# Mux_Demux.net
KiCad netlist of a schematic drawn in Altium Designer
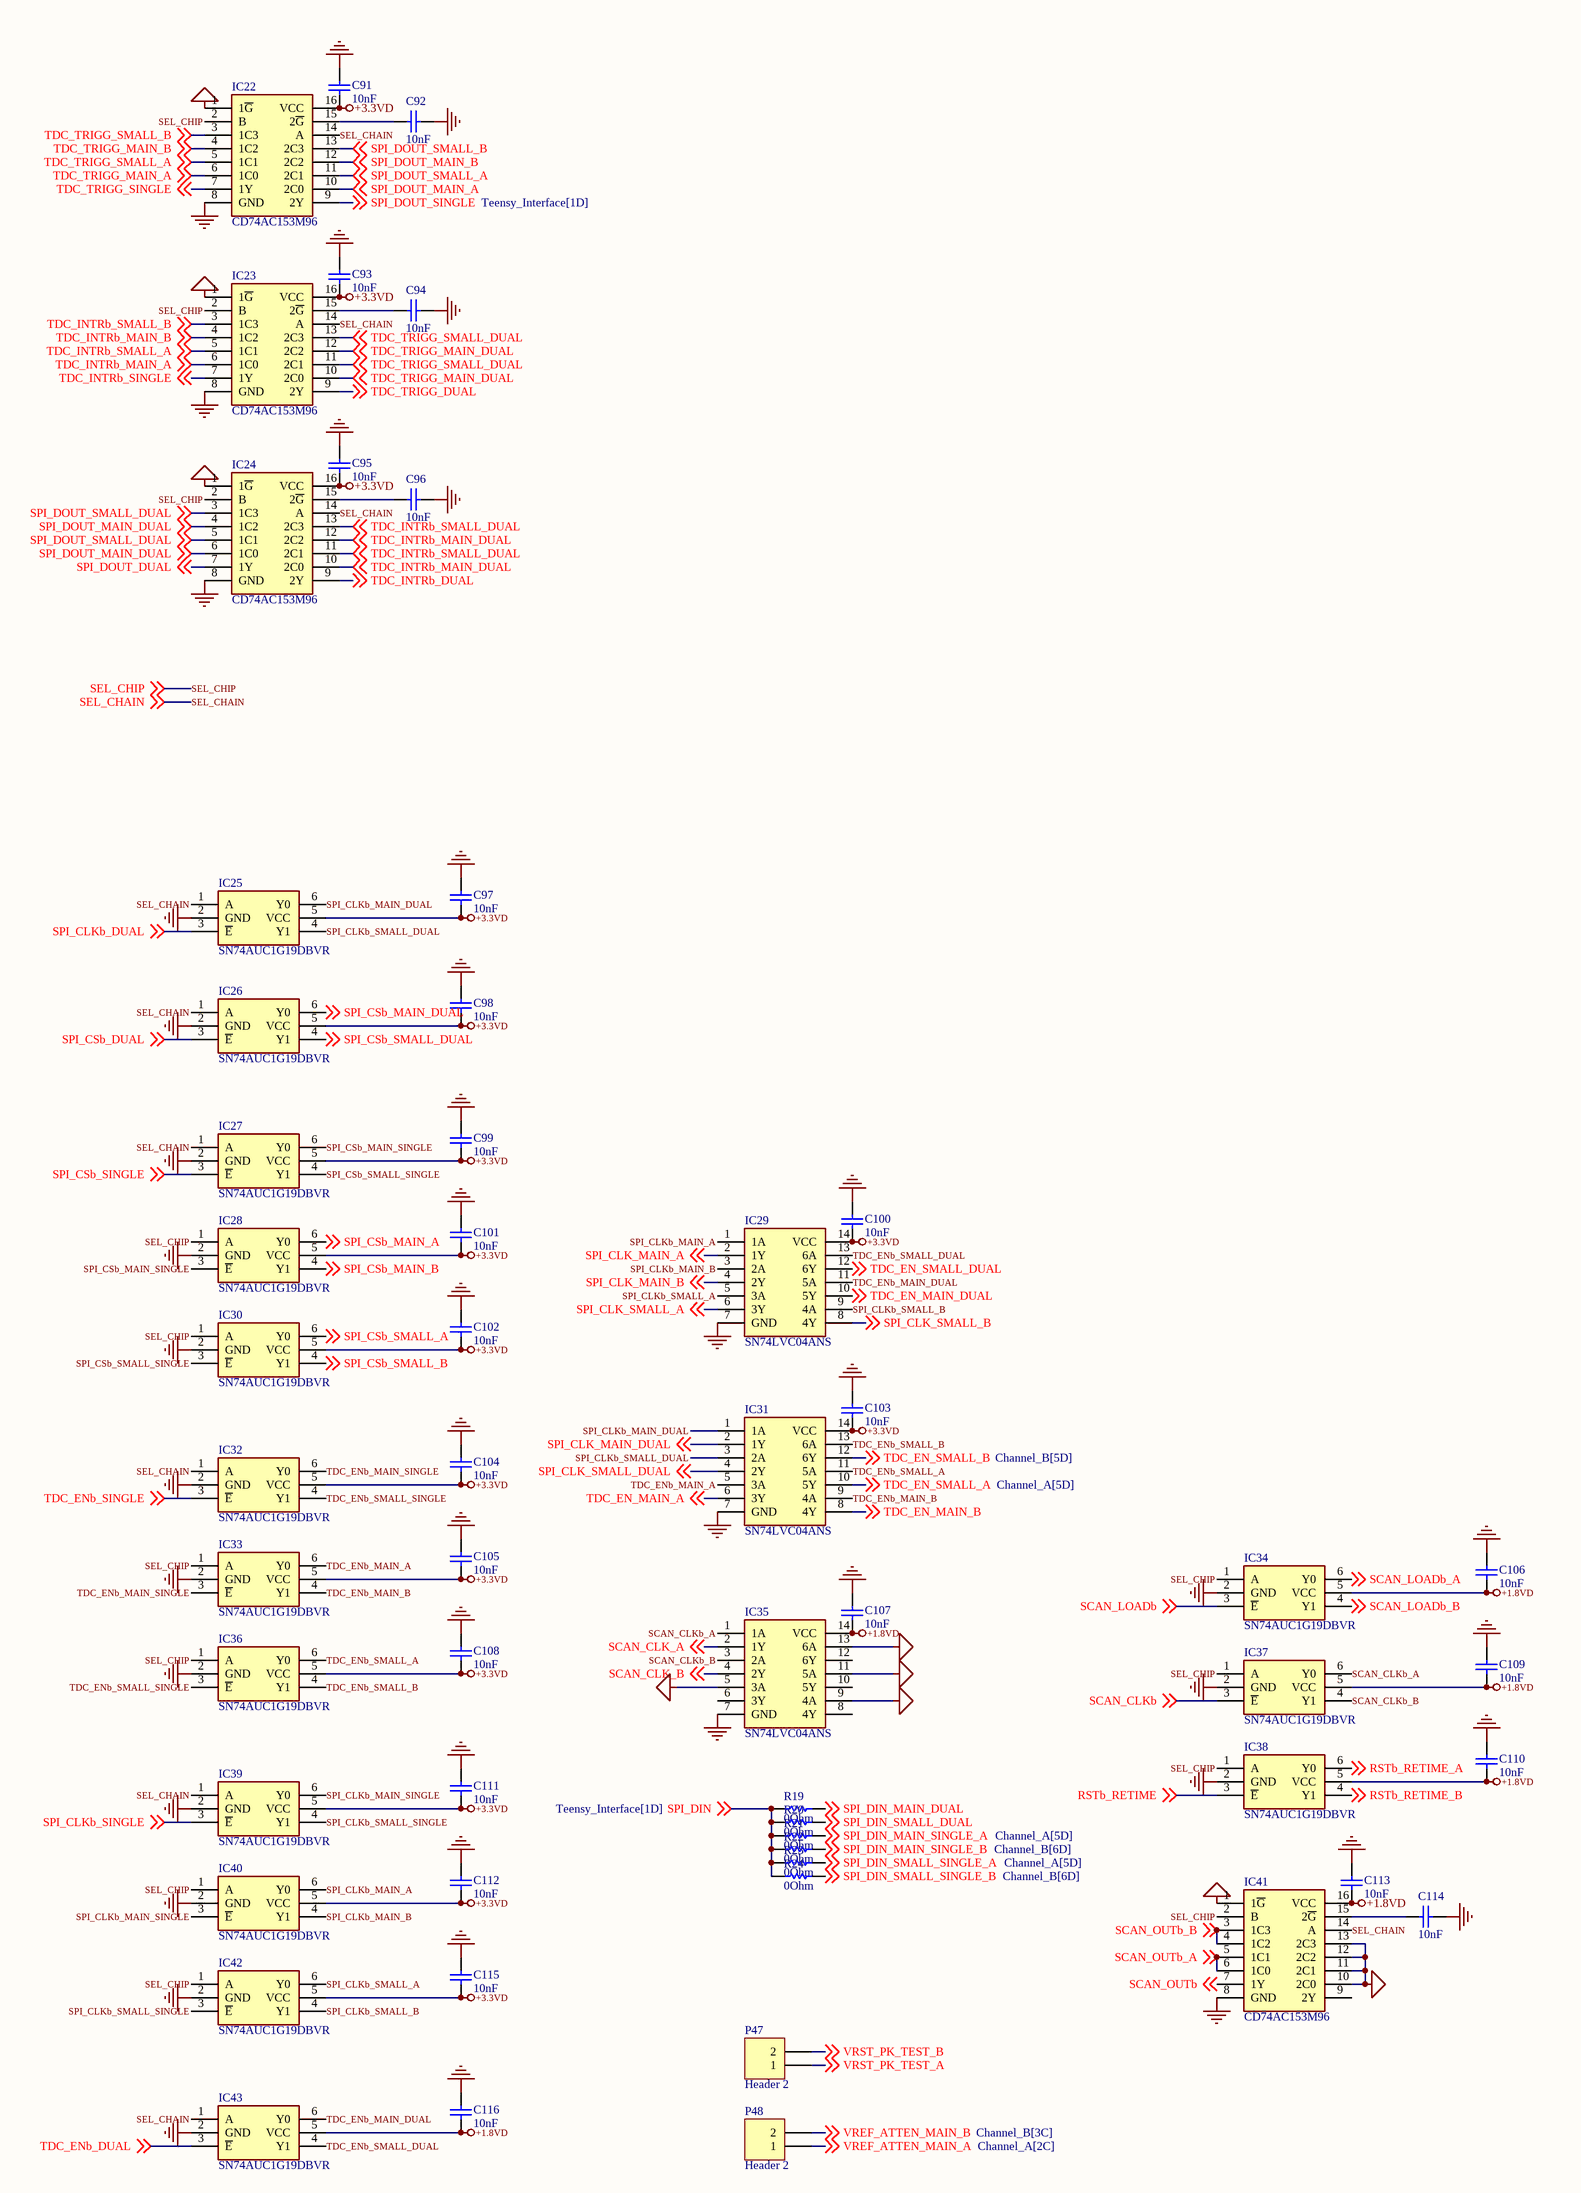
[diagram p0: Mux_Demux.SchDoc]

(export (version "E")
  (design (tool "Eeschema 10.0.6"))
  (components
    (comp (ref "C91")
      (value "10nF")
      (footprint "CAPC1608X90X35ML10T15")
      (description "0603")
      (fields (field (name "MANUFACTURER") "Murata"))
      (libsource (lib "Altium Content Vault") (part "CAP-NP-2"))
    )
    (comp (ref "C92")
      (value "10nF")
      (footprint "CAPC1608X90X35ML10T15")
      (description "0603")
      (fields (field (name "MANUFACTURER") "Murata"))
      (libsource (lib "Altium Content Vault") (part "CAP-NP-2"))
    )
    (comp (ref "C93")
      (value "10nF")
      (footprint "CAPC1608X90X35ML10T15")
      (description "0603")
      (fields (field (name "MANUFACTURER") "Murata"))
      (libsource (lib "Altium Content Vault") (part "CAP-NP-2"))
    )
    (comp (ref "C94")
      (value "10nF")
      (footprint "CAPC1608X90X35ML10T15")
      (description "0603")
      (fields (field (name "MANUFACTURER") "Murata"))
      (libsource (lib "Altium Content Vault") (part "CAP-NP-2"))
    )
    (comp (ref "C95")
      (value "10nF")
      (footprint "CAPC1608X90X35ML10T15")
      (description "0603")
      (fields (field (name "MANUFACTURER") "Murata"))
      (libsource (lib "Altium Content Vault") (part "CAP-NP-2"))
    )
    (comp (ref "C96")
      (value "10nF")
      (footprint "CAPC1608X90X35ML10T15")
      (description "0603")
      (fields (field (name "MANUFACTURER") "Murata"))
      (libsource (lib "Altium Content Vault") (part "CAP-NP-2"))
    )
    (comp (ref "C97")
      (value "10nF")
      (footprint "CAPC1608X90X35ML10T15")
      (description "0603")
      (fields (field (name "MANUFACTURER") "Murata"))
      (libsource (lib "Altium Content Vault") (part "CAP-NP-2"))
    )
    (comp (ref "C98")
      (value "10nF")
      (footprint "CAPC1608X90X35ML10T15")
      (description "0603")
      (fields (field (name "MANUFACTURER") "Murata"))
      (libsource (lib "Altium Content Vault") (part "CAP-NP-2"))
    )
    (comp (ref "C99")
      (value "10nF")
      (footprint "CAPC1608X90X35ML10T15")
      (description "0603")
      (fields (field (name "MANUFACTURER") "Murata"))
      (libsource (lib "Altium Content Vault") (part "CAP-NP-2"))
    )
    (comp (ref "C100")
      (value "10nF")
      (footprint "CAPC1608X90X35ML10T15")
      (description "0603")
      (fields (field (name "MANUFACTURER") "Murata"))
      (libsource (lib "Altium Content Vault") (part "CAP-NP-2"))
    )
    (comp (ref "C101")
      (value "10nF")
      (footprint "CAPC1608X90X35ML10T15")
      (description "0603")
      (fields (field (name "MANUFACTURER") "Murata"))
      (libsource (lib "Altium Content Vault") (part "CAP-NP-2"))
    )
    (comp (ref "C102")
      (value "10nF")
      (footprint "CAPC1608X90X35ML10T15")
      (description "0603")
      (fields (field (name "MANUFACTURER") "Murata"))
      (libsource (lib "Altium Content Vault") (part "CAP-NP-2"))
    )
    (comp (ref "C103")
      (value "10nF")
      (footprint "CAPC1608X90X35ML10T15")
      (description "0603")
      (fields (field (name "MANUFACTURER") "Murata"))
      (libsource (lib "Altium Content Vault") (part "CAP-NP-2"))
    )
    (comp (ref "C104")
      (value "10nF")
      (footprint "CAPC1608X90X35ML10T15")
      (description "0603")
      (fields (field (name "MANUFACTURER") "Murata"))
      (libsource (lib "Altium Content Vault") (part "CAP-NP-2"))
    )
    (comp (ref "C105")
      (value "10nF")
      (footprint "CAPC1608X90X35ML10T15")
      (description "0603")
      (fields (field (name "MANUFACTURER") "Murata"))
      (libsource (lib "Altium Content Vault") (part "CAP-NP-2"))
    )
    (comp (ref "C106")
      (value "10nF")
      (footprint "CAPC1608X90X35ML10T15")
      (description "0603")
      (fields (field (name "MANUFACTURER") "Murata"))
      (libsource (lib "Altium Content Vault") (part "CAP-NP-2"))
    )
    (comp (ref "C107")
      (value "10nF")
      (footprint "CAPC1608X90X35ML10T15")
      (description "0603")
      (fields (field (name "MANUFACTURER") "Murata"))
      (libsource (lib "Altium Content Vault") (part "CAP-NP-2"))
    )
    (comp (ref "C108")
      (value "10nF")
      (footprint "CAPC1608X90X35ML10T15")
      (description "0603")
      (fields (field (name "MANUFACTURER") "Murata"))
      (libsource (lib "Altium Content Vault") (part "CAP-NP-2"))
    )
    (comp (ref "C109")
      (value "10nF")
      (footprint "CAPC1608X90X35ML10T15")
      (description "0603")
      (fields (field (name "MANUFACTURER") "Murata"))
      (libsource (lib "Altium Content Vault") (part "CAP-NP-2"))
    )
    (comp (ref "C110")
      (value "10nF")
      (footprint "CAPC1608X90X35ML10T15")
      (description "0603")
      (fields (field (name "MANUFACTURER") "Murata"))
      (libsource (lib "Altium Content Vault") (part "CAP-NP-2"))
    )
    (comp (ref "C111")
      (value "10nF")
      (footprint "CAPC1608X90X35ML10T15")
      (description "0603")
      (fields (field (name "MANUFACTURER") "Murata"))
      (libsource (lib "Altium Content Vault") (part "CAP-NP-2"))
    )
    (comp (ref "C112")
      (value "10nF")
      (footprint "CAPC1608X90X35ML10T15")
      (description "0603")
      (fields (field (name "MANUFACTURER") "Murata"))
      (libsource (lib "Altium Content Vault") (part "CAP-NP-2"))
    )
    (comp (ref "C113")
      (value "10nF")
      (footprint "CAPC1608X90X35ML10T15")
      (description "0603")
      (fields (field (name "MANUFACTURER") "Murata"))
      (libsource (lib "Altium Content Vault") (part "CAP-NP-2"))
    )
    (comp (ref "C114")
      (value "10nF")
      (footprint "CAPC1608X90X35ML10T15")
      (description "0603")
      (fields (field (name "MANUFACTURER") "Murata"))
      (libsource (lib "Altium Content Vault") (part "CAP-NP-2"))
    )
    (comp (ref "C115")
      (value "10nF")
      (footprint "CAPC1608X90X35ML10T15")
      (description "0603")
      (fields (field (name "MANUFACTURER") "Murata"))
      (libsource (lib "Altium Content Vault") (part "CAP-NP-2"))
    )
    (comp (ref "C116")
      (value "10nF")
      (footprint "CAPC1608X90X35ML10T15")
      (description "0603")
      (fields (field (name "MANUFACTURER") "Murata"))
      (libsource (lib "Altium Content Vault") (part "CAP-NP-2"))
    )
    (comp (ref "IC22")
      (value "CD74AC153M96")
      (footprint "SamacSys:SOIC127P600X175-16N")
      (description "Encoders, Decoders, Multiplexers & Demultiplexers Dual 4-Input")
      (fields (field (name "MOUSER PART NUMBER") "595-CD74AC153M96"))
      (libsource (lib "*") (part "CD74AC153M96"))
    )
    (comp (ref "IC23")
      (value "CD74AC153M96")
      (footprint "SamacSys:SOIC127P600X175-16N")
      (description "Encoders, Decoders, Multiplexers & Demultiplexers Dual 4-Input")
      (fields (field (name "MOUSER PART NUMBER") "595-CD74AC153M96"))
      (libsource (lib "*") (part "CD74AC153M96"))
    )
    (comp (ref "IC24")
      (value "CD74AC153M96")
      (footprint "SamacSys:SOIC127P600X175-16N")
      (description "Encoders, Decoders, Multiplexers & Demultiplexers Dual 4-Input")
      (fields (field (name "MOUSER PART NUMBER") "595-CD74AC153M96"))
      (libsource (lib "*") (part "CD74AC153M96"))
    )
    (comp (ref "IC25")
      (value "SN74AUC1G19DBVR")
      (footprint "SamacSys:SOT95P280X145-6N")
      (description "Encoders, Decoders, Multiplexers & Demultiplexers 1 of 2 Decoder DeMultxe")
      (fields (field (name "MOUSER PART NUMBER") "595-SN74AUC1G19DBVR"))
      (libsource (lib "*") (part "SN74AUC1G19DBVR"))
    )
    (comp (ref "IC26")
      (value "SN74AUC1G19DBVR")
      (footprint "SamacSys:SOT95P280X145-6N")
      (description "Encoders, Decoders, Multiplexers & Demultiplexers 1 of 2 Decoder DeMultxe")
      (fields (field (name "MOUSER PART NUMBER") "595-SN74AUC1G19DBVR"))
      (libsource (lib "*") (part "SN74AUC1G19DBVR"))
    )
    (comp (ref "IC27")
      (value "SN74AUC1G19DBVR")
      (footprint "SamacSys:SOT95P280X145-6N")
      (description "Encoders, Decoders, Multiplexers & Demultiplexers 1 of 2 Decoder DeMultxe")
      (fields (field (name "MOUSER PART NUMBER") "595-SN74AUC1G19DBVR"))
      (libsource (lib "*") (part "SN74AUC1G19DBVR"))
    )
    (comp (ref "IC28")
      (value "SN74AUC1G19DBVR")
      (footprint "SamacSys:SOT95P280X145-6N")
      (description "Encoders, Decoders, Multiplexers & Demultiplexers 1 of 2 Decoder DeMultxe")
      (fields (field (name "MOUSER PART NUMBER") "595-SN74AUC1G19DBVR"))
      (libsource (lib "*") (part "SN74AUC1G19DBVR"))
    )
    (comp (ref "IC29")
      (value "SN74LVC04ANS")
      (footprint "SamacSys:SOIC127P780X200-14N")
      (description "Inverters Hex Inverter")
      (fields (field (name "MOUSER PART NUMBER") "595-SN74LVC04ANS"))
      (libsource (lib "*") (part "SN74LVC04ANS"))
    )
    (comp (ref "IC30")
      (value "SN74AUC1G19DBVR")
      (footprint "SamacSys:SOT95P280X145-6N")
      (description "Encoders, Decoders, Multiplexers & Demultiplexers 1 of 2 Decoder DeMultxe")
      (fields (field (name "MOUSER PART NUMBER") "595-SN74AUC1G19DBVR"))
      (libsource (lib "*") (part "SN74AUC1G19DBVR"))
    )
    (comp (ref "IC31")
      (value "SN74LVC04ANS")
      (footprint "SamacSys:SOIC127P780X200-14N")
      (description "Inverters Hex Inverter")
      (fields (field (name "MOUSER PART NUMBER") "595-SN74LVC04ANS"))
      (libsource (lib "*") (part "SN74LVC04ANS"))
    )
    (comp (ref "IC32")
      (value "SN74AUC1G19DBVR")
      (footprint "SamacSys:SOT95P280X145-6N")
      (description "Encoders, Decoders, Multiplexers & Demultiplexers 1 of 2 Decoder DeMultxe")
      (fields (field (name "MOUSER PART NUMBER") "595-SN74AUC1G19DBVR"))
      (libsource (lib "*") (part "SN74AUC1G19DBVR"))
    )
    (comp (ref "IC33")
      (value "SN74AUC1G19DBVR")
      (footprint "SamacSys:SOT95P280X145-6N")
      (description "Encoders, Decoders, Multiplexers & Demultiplexers 1 of 2 Decoder DeMultxe")
      (fields (field (name "MOUSER PART NUMBER") "595-SN74AUC1G19DBVR"))
      (libsource (lib "*") (part "SN74AUC1G19DBVR"))
    )
    (comp (ref "IC34")
      (value "SN74AUC1G19DBVR")
      (footprint "SamacSys:SOT95P280X145-6N")
      (description "Encoders, Decoders, Multiplexers & Demultiplexers 1 of 2 Decoder DeMultxe")
      (fields (field (name "MOUSER PART NUMBER") "595-SN74AUC1G19DBVR"))
      (libsource (lib "*") (part "SN74AUC1G19DBVR"))
    )
    (comp (ref "IC35")
      (value "SN74LVC04ANS")
      (footprint "SamacSys:SOIC127P780X200-14N")
      (description "Inverters Hex Inverter")
      (fields (field (name "MOUSER PART NUMBER") "595-SN74LVC04ANS"))
      (libsource (lib "*") (part "SN74LVC04ANS"))
    )
    (comp (ref "IC36")
      (value "SN74AUC1G19DBVR")
      (footprint "SamacSys:SOT95P280X145-6N")
      (description "Encoders, Decoders, Multiplexers & Demultiplexers 1 of 2 Decoder DeMultxe")
      (fields (field (name "MOUSER PART NUMBER") "595-SN74AUC1G19DBVR"))
      (libsource (lib "*") (part "SN74AUC1G19DBVR"))
    )
    (comp (ref "IC37")
      (value "SN74AUC1G19DBVR")
      (footprint "SamacSys:SOT95P280X145-6N")
      (description "Encoders, Decoders, Multiplexers & Demultiplexers 1 of 2 Decoder DeMultxe")
      (fields (field (name "MOUSER PART NUMBER") "595-SN74AUC1G19DBVR"))
      (libsource (lib "*") (part "SN74AUC1G19DBVR"))
    )
    (comp (ref "IC38")
      (value "SN74AUC1G19DBVR")
      (footprint "SamacSys:SOT95P280X145-6N")
      (description "Encoders, Decoders, Multiplexers & Demultiplexers 1 of 2 Decoder DeMultxe")
      (fields (field (name "MOUSER PART NUMBER") "595-SN74AUC1G19DBVR"))
      (libsource (lib "*") (part "SN74AUC1G19DBVR"))
    )
    (comp (ref "IC39")
      (value "SN74AUC1G19DBVR")
      (footprint "SamacSys:SOT95P280X145-6N")
      (description "Encoders, Decoders, Multiplexers & Demultiplexers 1 of 2 Decoder DeMultxe")
      (fields (field (name "MOUSER PART NUMBER") "595-SN74AUC1G19DBVR"))
      (libsource (lib "*") (part "SN74AUC1G19DBVR"))
    )
    (comp (ref "IC40")
      (value "SN74AUC1G19DBVR")
      (footprint "SamacSys:SOT95P280X145-6N")
      (description "Encoders, Decoders, Multiplexers & Demultiplexers 1 of 2 Decoder DeMultxe")
      (fields (field (name "MOUSER PART NUMBER") "595-SN74AUC1G19DBVR"))
      (libsource (lib "*") (part "SN74AUC1G19DBVR"))
    )
    (comp (ref "IC41")
      (value "CD74AC153M96")
      (footprint "SamacSys:SOIC127P600X175-16N")
      (description "Encoders, Decoders, Multiplexers & Demultiplexers Dual 4-Input")
      (fields (field (name "MOUSER PART NUMBER") "595-CD74AC153M96"))
      (libsource (lib "*") (part "CD74AC153M96"))
    )
    (comp (ref "IC42")
      (value "SN74AUC1G19DBVR")
      (footprint "SamacSys:SOT95P280X145-6N")
      (description "Encoders, Decoders, Multiplexers & Demultiplexers 1 of 2 Decoder DeMultxe")
      (fields (field (name "MOUSER PART NUMBER") "595-SN74AUC1G19DBVR"))
      (libsource (lib "*") (part "SN74AUC1G19DBVR"))
    )
    (comp (ref "IC43")
      (value "SN74AUC1G19DBVR")
      (footprint "SamacSys:SOT95P280X145-6N")
      (description "Encoders, Decoders, Multiplexers & Demultiplexers 1 of 2 Decoder DeMultxe")
      (fields (field (name "MOUSER PART NUMBER") "595-SN74AUC1G19DBVR"))
      (libsource (lib "*") (part "SN74AUC1G19DBVR"))
    )
    (comp (ref "P47")
      (value "Header 2")
      (footprint "HDR1X2")
      (description "Header, 2-Pin")
      (fields (field (name "PUBLISHER") "Altium Limited"))
      (libsource (lib "Miscellaneous Connectors") (part "Header 2"))
    )
    (comp (ref "P48")
      (value "Header 2")
      (footprint "HDR1X2")
      (description "Header, 2-Pin")
      (fields (field (name "PUBLISHER") "Altium Limited"))
      (libsource (lib "Miscellaneous Connectors") (part "Header 2"))
    )
    (comp (ref "R19")
      (value "0Ohm")
      (footprint "RESC1609X50X30NL8T20")
      (description "0603")
      (fields (field (name "MANUFACTURER") "Vishay Semiconductor"))
      (libsource (lib "Altium Content Vault") (part "RES-2"))
    )
    (comp (ref "R20")
      (value "0Ohm")
      (footprint "RESC1609X50X30NL8T20")
      (description "0603")
      (fields (field (name "MANUFACTURER") "Vishay Semiconductor"))
      (libsource (lib "Altium Content Vault") (part "RES-2"))
    )
    (comp (ref "R21")
      (value "0Ohm")
      (footprint "RESC1609X50X30NL8T20")
      (description "0603")
      (fields (field (name "MANUFACTURER") "Vishay Semiconductor"))
      (libsource (lib "Altium Content Vault") (part "RES-2"))
    )
    (comp (ref "R22")
      (value "0Ohm")
      (footprint "RESC1609X50X30NL8T20")
      (description "0603")
      (fields (field (name "MANUFACTURER") "Vishay Semiconductor"))
      (libsource (lib "Altium Content Vault") (part "RES-2"))
    )
    (comp (ref "R23")
      (value "0Ohm")
      (footprint "RESC1609X50X30NL8T20")
      (description "0603")
      (fields (field (name "MANUFACTURER") "Vishay Semiconductor"))
      (libsource (lib "Altium Content Vault") (part "RES-2"))
    )
    (comp (ref "R24")
      (value "0Ohm")
      (footprint "RESC1609X50X30NL8T20")
      (description "0603")
      (fields (field (name "MANUFACTURER") "Vishay Semiconductor"))
      (libsource (lib "Altium Content Vault") (part "RES-2"))
    )
  )
  (nets
    (net (code "1") (name "+1.8VD") (class "Default")
      (node (ref "C106") (pin "1") (pinfunction "1_1") (pintype "passive"))
      (node (ref "C107") (pin "1") (pinfunction "1_1") (pintype "passive"))
      (node (ref "C109") (pin "1") (pinfunction "1_1") (pintype "passive"))
      (node (ref "C110") (pin "1") (pinfunction "1_1") (pintype "passive"))
      (node (ref "C113") (pin "1") (pinfunction "1_1") (pintype "passive"))
      (node (ref "C116") (pin "1") (pinfunction "1_1") (pintype "passive"))
      (node (ref "IC34") (pin "5") (pinfunction "VCC_5") (pintype "passive"))
      (node (ref "IC35") (pin "14") (pinfunction "VCC_14") (pintype "passive"))
      (node (ref "IC37") (pin "5") (pinfunction "VCC_5") (pintype "passive"))
      (node (ref "IC38") (pin "5") (pinfunction "VCC_5") (pintype "passive"))
      (node (ref "IC41") (pin "16") (pinfunction "VCC_16") (pintype "passive"))
      (node (ref "IC43") (pin "5") (pinfunction "VCC_5") (pintype "passive"))
    )
    (net (code "2") (name "+3.3VD") (class "Default")
      (node (ref "C100") (pin "1") (pinfunction "1_1") (pintype "passive"))
      (node (ref "C101") (pin "1") (pinfunction "1_1") (pintype "passive"))
      (node (ref "C102") (pin "1") (pinfunction "1_1") (pintype "passive"))
      (node (ref "C103") (pin "1") (pinfunction "1_1") (pintype "passive"))
      (node (ref "C104") (pin "1") (pinfunction "1_1") (pintype "passive"))
      (node (ref "C105") (pin "1") (pinfunction "1_1") (pintype "passive"))
      (node (ref "C108") (pin "1") (pinfunction "1_1") (pintype "passive"))
      (node (ref "C111") (pin "1") (pinfunction "1_1") (pintype "passive"))
      (node (ref "C112") (pin "1") (pinfunction "1_1") (pintype "passive"))
      (node (ref "C115") (pin "1") (pinfunction "1_1") (pintype "passive"))
      (node (ref "C91") (pin "1") (pinfunction "1_1") (pintype "passive"))
      (node (ref "C93") (pin "1") (pinfunction "1_1") (pintype "passive"))
      (node (ref "C95") (pin "1") (pinfunction "1_1") (pintype "passive"))
      (node (ref "C97") (pin "1") (pinfunction "1_1") (pintype "passive"))
      (node (ref "C98") (pin "1") (pinfunction "1_1") (pintype "passive"))
      (node (ref "C99") (pin "1") (pinfunction "1_1") (pintype "passive"))
      (node (ref "IC22") (pin "16") (pinfunction "VCC_16") (pintype "passive"))
      (node (ref "IC23") (pin "16") (pinfunction "VCC_16") (pintype "passive"))
      (node (ref "IC24") (pin "16") (pinfunction "VCC_16") (pintype "passive"))
      (node (ref "IC25") (pin "5") (pinfunction "VCC_5") (pintype "passive"))
      (node (ref "IC26") (pin "5") (pinfunction "VCC_5") (pintype "passive"))
      (node (ref "IC27") (pin "5") (pinfunction "VCC_5") (pintype "passive"))
      (node (ref "IC28") (pin "5") (pinfunction "VCC_5") (pintype "passive"))
      (node (ref "IC29") (pin "14") (pinfunction "VCC_14") (pintype "passive"))
      (node (ref "IC30") (pin "5") (pinfunction "VCC_5") (pintype "passive"))
      (node (ref "IC31") (pin "14") (pinfunction "VCC_14") (pintype "passive"))
      (node (ref "IC32") (pin "5") (pinfunction "VCC_5") (pintype "passive"))
      (node (ref "IC33") (pin "5") (pinfunction "VCC_5") (pintype "passive"))
      (node (ref "IC36") (pin "5") (pinfunction "VCC_5") (pintype "passive"))
      (node (ref "IC39") (pin "5") (pinfunction "VCC_5") (pintype "passive"))
      (node (ref "IC40") (pin "5") (pinfunction "VCC_5") (pintype "passive"))
      (node (ref "IC42") (pin "5") (pinfunction "VCC_5") (pintype "passive"))
    )
    (net (code "3") (name "/SCAN_CLKb_A") (class "Default")
      (node (ref "IC35") (pin "1") (pinfunction "1A_1") (pintype "passive"))
      (node (ref "IC37") (pin "6") (pinfunction "Y0_6") (pintype "passive"))
    )
    (net (code "4") (name "/SCAN_CLKb_B") (class "Default")
      (node (ref "IC35") (pin "3") (pinfunction "2A_3") (pintype "passive"))
      (node (ref "IC37") (pin "4") (pinfunction "Y1_4") (pintype "passive"))
    )
    (net (code "5") (name "/SPI_CLKb_MAIN_A") (class "Default")
      (node (ref "IC29") (pin "1") (pinfunction "1A_1") (pintype "passive"))
      (node (ref "IC40") (pin "6") (pinfunction "Y0_6") (pintype "passive"))
    )
    (net (code "6") (name "/SPI_CLKb_MAIN_B") (class "Default")
      (node (ref "IC29") (pin "3") (pinfunction "2A_3") (pintype "passive"))
      (node (ref "IC40") (pin "4") (pinfunction "Y1_4") (pintype "passive"))
    )
    (net (code "7") (name "/SPI_CLKb_MAIN_DUAL") (class "Default")
      (node (ref "IC25") (pin "6") (pinfunction "Y0_6") (pintype "passive"))
      (node (ref "IC31") (pin "1") (pinfunction "1A_1") (pintype "passive"))
    )
    (net (code "8") (name "/SPI_CLKb_MAIN_SINGLE") (class "Default")
      (node (ref "IC39") (pin "6") (pinfunction "Y0_6") (pintype "passive"))
      (node (ref "IC40") (pin "3") (pinfunction "~{E}_3") (pintype "passive"))
    )
    (net (code "9") (name "/SPI_CLKb_SMALL_A") (class "Default")
      (node (ref "IC29") (pin "5") (pinfunction "3A_5") (pintype "passive"))
      (node (ref "IC42") (pin "6") (pinfunction "Y0_6") (pintype "passive"))
    )
    (net (code "10") (name "/SPI_CLKb_SMALL_B") (class "Default")
      (node (ref "IC29") (pin "9") (pinfunction "4A_9") (pintype "passive"))
      (node (ref "IC42") (pin "4") (pinfunction "Y1_4") (pintype "passive"))
    )
    (net (code "11") (name "/SPI_CLKb_SMALL_DUAL") (class "Default")
      (node (ref "IC25") (pin "4") (pinfunction "Y1_4") (pintype "passive"))
      (node (ref "IC31") (pin "3") (pinfunction "2A_3") (pintype "passive"))
    )
    (net (code "12") (name "/SPI_CLKb_SMALL_SINGLE") (class "Default")
      (node (ref "IC39") (pin "4") (pinfunction "Y1_4") (pintype "passive"))
      (node (ref "IC42") (pin "3") (pinfunction "~{E}_3") (pintype "passive"))
    )
    (net (code "13") (name "/SPI_CSb_MAIN_SINGLE") (class "Default")
      (node (ref "IC27") (pin "6") (pinfunction "Y0_6") (pintype "passive"))
      (node (ref "IC28") (pin "3") (pinfunction "~{E}_3") (pintype "passive"))
    )
    (net (code "14") (name "/SPI_CSb_SMALL_SINGLE") (class "Default")
      (node (ref "IC27") (pin "4") (pinfunction "Y1_4") (pintype "passive"))
      (node (ref "IC30") (pin "3") (pinfunction "~{E}_3") (pintype "passive"))
    )
    (net (code "15") (name "/TDC_ENb_MAIN_A") (class "Default")
      (node (ref "IC31") (pin "5") (pinfunction "3A_5") (pintype "passive"))
      (node (ref "IC33") (pin "6") (pinfunction "Y0_6") (pintype "passive"))
    )
    (net (code "16") (name "/TDC_ENb_MAIN_B") (class "Default")
      (node (ref "IC31") (pin "9") (pinfunction "4A_9") (pintype "passive"))
      (node (ref "IC33") (pin "4") (pinfunction "Y1_4") (pintype "passive"))
    )
    (net (code "17") (name "/TDC_ENb_MAIN_DUAL") (class "Default")
      (node (ref "IC29") (pin "11") (pinfunction "5A_11") (pintype "passive"))
      (node (ref "IC43") (pin "6") (pinfunction "Y0_6") (pintype "passive"))
    )
    (net (code "18") (name "/TDC_ENb_MAIN_SINGLE") (class "Default")
      (node (ref "IC32") (pin "6") (pinfunction "Y0_6") (pintype "passive"))
      (node (ref "IC33") (pin "3") (pinfunction "~{E}_3") (pintype "passive"))
    )
    (net (code "19") (name "/TDC_ENb_SMALL_A") (class "Default")
      (node (ref "IC31") (pin "11") (pinfunction "5A_11") (pintype "passive"))
      (node (ref "IC36") (pin "6") (pinfunction "Y0_6") (pintype "passive"))
    )
    (net (code "20") (name "/TDC_ENb_SMALL_B") (class "Default")
      (node (ref "IC31") (pin "13") (pinfunction "6A_13") (pintype "passive"))
      (node (ref "IC36") (pin "4") (pinfunction "Y1_4") (pintype "passive"))
    )
    (net (code "21") (name "/TDC_ENb_SMALL_DUAL") (class "Default")
      (node (ref "IC29") (pin "13") (pinfunction "6A_13") (pintype "passive"))
      (node (ref "IC43") (pin "4") (pinfunction "Y1_4") (pintype "passive"))
    )
    (net (code "22") (name "/TDC_ENb_SMALL_SINGLE") (class "Default")
      (node (ref "IC32") (pin "4") (pinfunction "Y1_4") (pintype "passive"))
      (node (ref "IC36") (pin "3") (pinfunction "~{E}_3") (pintype "passive"))
    )
    (net (code "23") (name "GND") (class "Default")
      (node (ref "C100") (pin "2") (pinfunction "2_2") (pintype "passive"))
      (node (ref "C101") (pin "2") (pinfunction "2_2") (pintype "passive"))
      (node (ref "C102") (pin "2") (pinfunction "2_2") (pintype "passive"))
      (node (ref "C103") (pin "2") (pinfunction "2_2") (pintype "passive"))
      (node (ref "C104") (pin "2") (pinfunction "2_2") (pintype "passive"))
      (node (ref "C105") (pin "2") (pinfunction "2_2") (pintype "passive"))
      (node (ref "C106") (pin "2") (pinfunction "2_2") (pintype "passive"))
      (node (ref "C107") (pin "2") (pinfunction "2_2") (pintype "passive"))
      (node (ref "C108") (pin "2") (pinfunction "2_2") (pintype "passive"))
      (node (ref "C109") (pin "2") (pinfunction "2_2") (pintype "passive"))
      (node (ref "C110") (pin "2") (pinfunction "2_2") (pintype "passive"))
      (node (ref "C111") (pin "2") (pinfunction "2_2") (pintype "passive"))
      (node (ref "C112") (pin "2") (pinfunction "2_2") (pintype "passive"))
      (node (ref "C113") (pin "2") (pinfunction "2_2") (pintype "passive"))
      (node (ref "C114") (pin "2") (pinfunction "2_2") (pintype "passive"))
      (node (ref "C115") (pin "2") (pinfunction "2_2") (pintype "passive"))
      (node (ref "C116") (pin "2") (pinfunction "2_2") (pintype "passive"))
      (node (ref "C91") (pin "2") (pinfunction "2_2") (pintype "passive"))
      (node (ref "C92") (pin "2") (pinfunction "2_2") (pintype "passive"))
      (node (ref "C93") (pin "2") (pinfunction "2_2") (pintype "passive"))
      (node (ref "C94") (pin "2") (pinfunction "2_2") (pintype "passive"))
      (node (ref "C95") (pin "2") (pinfunction "2_2") (pintype "passive"))
      (node (ref "C96") (pin "2") (pinfunction "2_2") (pintype "passive"))
      (node (ref "C97") (pin "2") (pinfunction "2_2") (pintype "passive"))
      (node (ref "C98") (pin "2") (pinfunction "2_2") (pintype "passive"))
      (node (ref "C99") (pin "2") (pinfunction "2_2") (pintype "passive"))
      (node (ref "IC22") (pin "1") (pinfunction "1~{G}_1") (pintype "passive"))
      (node (ref "IC22") (pin "8") (pinfunction "GND_8") (pintype "passive"))
      (node (ref "IC23") (pin "1") (pinfunction "1~{G}_1") (pintype "passive"))
      (node (ref "IC23") (pin "8") (pinfunction "GND_8") (pintype "passive"))
      (node (ref "IC24") (pin "1") (pinfunction "1~{G}_1") (pintype "passive"))
      (node (ref "IC24") (pin "8") (pinfunction "GND_8") (pintype "passive"))
      (node (ref "IC25") (pin "2") (pinfunction "GND_2") (pintype "passive"))
      (node (ref "IC26") (pin "2") (pinfunction "GND_2") (pintype "passive"))
      (node (ref "IC27") (pin "2") (pinfunction "GND_2") (pintype "passive"))
      (node (ref "IC28") (pin "2") (pinfunction "GND_2") (pintype "passive"))
      (node (ref "IC29") (pin "7") (pinfunction "GND_7") (pintype "passive"))
      (node (ref "IC30") (pin "2") (pinfunction "GND_2") (pintype "passive"))
      (node (ref "IC31") (pin "7") (pinfunction "GND_7") (pintype "passive"))
      (node (ref "IC32") (pin "2") (pinfunction "GND_2") (pintype "passive"))
      (node (ref "IC33") (pin "2") (pinfunction "GND_2") (pintype "passive"))
      (node (ref "IC34") (pin "2") (pinfunction "GND_2") (pintype "passive"))
      (node (ref "IC35") (pin "11") (pinfunction "5A_11") (pintype "passive"))
      (node (ref "IC35") (pin "13") (pinfunction "6A_13") (pintype "passive"))
      (node (ref "IC35") (pin "5") (pinfunction "3A_5") (pintype "passive"))
      (node (ref "IC35") (pin "7") (pinfunction "GND_7") (pintype "passive"))
      (node (ref "IC35") (pin "9") (pinfunction "4A_9") (pintype "passive"))
      (node (ref "IC36") (pin "2") (pinfunction "GND_2") (pintype "passive"))
      (node (ref "IC37") (pin "2") (pinfunction "GND_2") (pintype "passive"))
      (node (ref "IC38") (pin "2") (pinfunction "GND_2") (pintype "passive"))
      (node (ref "IC39") (pin "2") (pinfunction "GND_2") (pintype "passive"))
      (node (ref "IC40") (pin "2") (pinfunction "GND_2") (pintype "passive"))
      (node (ref "IC41") (pin "1") (pinfunction "1~{G}_1") (pintype "passive"))
      (node (ref "IC41") (pin "10") (pinfunction "2C0_10") (pintype "passive"))
      (node (ref "IC41") (pin "11") (pinfunction "2C1_11") (pintype "passive"))
      (node (ref "IC41") (pin "12") (pinfunction "2C2_12") (pintype "passive"))
      (node (ref "IC41") (pin "13") (pinfunction "2C3_13") (pintype "passive"))
      (node (ref "IC41") (pin "8") (pinfunction "GND_8") (pintype "passive"))
      (node (ref "IC42") (pin "2") (pinfunction "GND_2") (pintype "passive"))
      (node (ref "IC43") (pin "2") (pinfunction "GND_2") (pintype "passive"))
    )
    (net (code "24") (name "Net-(IC22-2~{G})") (class "Default")
      (node (ref "C92") (pin "1") (pinfunction "1_1") (pintype "passive"))
      (node (ref "IC22") (pin "15") (pinfunction "2~{G}_15") (pintype "passive"))
    )
    (net (code "25") (name "Net-(IC23-2~{G})") (class "Default")
      (node (ref "C94") (pin "1") (pinfunction "1_1") (pintype "passive"))
      (node (ref "IC23") (pin "15") (pinfunction "2~{G}_15") (pintype "passive"))
    )
    (net (code "26") (name "Net-(IC24-2~{G})") (class "Default")
      (node (ref "C96") (pin "1") (pinfunction "1_1") (pintype "passive"))
      (node (ref "IC24") (pin "15") (pinfunction "2~{G}_15") (pintype "passive"))
    )
    (net (code "27") (name "Net-(IC41-2~{G})") (class "Default")
      (node (ref "C114") (pin "1") (pinfunction "1_1") (pintype "passive"))
      (node (ref "IC41") (pin "15") (pinfunction "2~{G}_15") (pintype "passive"))
    )
    (net (code "28") (name "RSTb_RETIME") (class "Default")
      (node (ref "IC38") (pin "3") (pinfunction "~{E}_3") (pintype "passive"))
    )
    (net (code "29") (name "RSTb_RETIME_A") (class "Default")
      (node (ref "IC38") (pin "6") (pinfunction "Y0_6") (pintype "passive"))
    )
    (net (code "30") (name "RSTb_RETIME_B") (class "Default")
      (node (ref "IC38") (pin "4") (pinfunction "Y1_4") (pintype "passive"))
    )
    (net (code "31") (name "SCAN_CLK_A") (class "Default")
      (node (ref "IC35") (pin "2") (pinfunction "1Y_2") (pintype "passive"))
    )
    (net (code "32") (name "SCAN_CLK_B") (class "Default")
      (node (ref "IC35") (pin "4") (pinfunction "2Y_4") (pintype "passive"))
    )
    (net (code "33") (name "SCAN_CLKb") (class "Default")
      (node (ref "IC37") (pin "3") (pinfunction "~{E}_3") (pintype "passive"))
    )
    (net (code "34") (name "SCAN_LOADb") (class "Default")
      (node (ref "IC34") (pin "3") (pinfunction "~{E}_3") (pintype "passive"))
    )
    (net (code "35") (name "SCAN_LOADb_A") (class "Default")
      (node (ref "IC34") (pin "6") (pinfunction "Y0_6") (pintype "passive"))
    )
    (net (code "36") (name "SCAN_LOADb_B") (class "Default")
      (node (ref "IC34") (pin "4") (pinfunction "Y1_4") (pintype "passive"))
    )
    (net (code "37") (name "SCAN_OUTb") (class "Default")
      (node (ref "IC41") (pin "7") (pinfunction "1Y_7") (pintype "passive"))
    )
    (net (code "38") (name "SCAN_OUTb_A") (class "Default")
      (node (ref "IC41") (pin "5") (pinfunction "1C1_5") (pintype "passive"))
      (node (ref "IC41") (pin "6") (pinfunction "1C0_6") (pintype "passive"))
    )
    (net (code "39") (name "SCAN_OUTb_B") (class "Default")
      (node (ref "IC41") (pin "3") (pinfunction "1C3_3") (pintype "passive"))
      (node (ref "IC41") (pin "4") (pinfunction "1C2_4") (pintype "passive"))
    )
    (net (code "40") (name "SEL_CHAIN") (class "Default")
      (node (ref "IC22") (pin "14") (pinfunction "A_14") (pintype "passive"))
      (node (ref "IC23") (pin "14") (pinfunction "A_14") (pintype "passive"))
      (node (ref "IC24") (pin "14") (pinfunction "A_14") (pintype "passive"))
      (node (ref "IC25") (pin "1") (pinfunction "A_1") (pintype "passive"))
      (node (ref "IC26") (pin "1") (pinfunction "A_1") (pintype "passive"))
      (node (ref "IC27") (pin "1") (pinfunction "A_1") (pintype "passive"))
      (node (ref "IC32") (pin "1") (pinfunction "A_1") (pintype "passive"))
      (node (ref "IC39") (pin "1") (pinfunction "A_1") (pintype "passive"))
      (node (ref "IC41") (pin "14") (pinfunction "A_14") (pintype "passive"))
      (node (ref "IC43") (pin "1") (pinfunction "A_1") (pintype "passive"))
    )
    (net (code "41") (name "SEL_CHIP") (class "Default")
      (node (ref "IC22") (pin "2") (pinfunction "B_2") (pintype "passive"))
      (node (ref "IC23") (pin "2") (pinfunction "B_2") (pintype "passive"))
      (node (ref "IC24") (pin "2") (pinfunction "B_2") (pintype "passive"))
      (node (ref "IC28") (pin "1") (pinfunction "A_1") (pintype "passive"))
      (node (ref "IC30") (pin "1") (pinfunction "A_1") (pintype "passive"))
      (node (ref "IC33") (pin "1") (pinfunction "A_1") (pintype "passive"))
      (node (ref "IC34") (pin "1") (pinfunction "A_1") (pintype "passive"))
      (node (ref "IC36") (pin "1") (pinfunction "A_1") (pintype "passive"))
      (node (ref "IC37") (pin "1") (pinfunction "A_1") (pintype "passive"))
      (node (ref "IC38") (pin "1") (pinfunction "A_1") (pintype "passive"))
      (node (ref "IC40") (pin "1") (pinfunction "A_1") (pintype "passive"))
      (node (ref "IC41") (pin "2") (pinfunction "B_2") (pintype "passive"))
      (node (ref "IC42") (pin "1") (pinfunction "A_1") (pintype "passive"))
    )
    (net (code "42") (name "SPI_CLK_MAIN_A") (class "Default")
      (node (ref "IC29") (pin "2") (pinfunction "1Y_2") (pintype "passive"))
    )
    (net (code "43") (name "SPI_CLK_MAIN_B") (class "Default")
      (node (ref "IC29") (pin "4") (pinfunction "2Y_4") (pintype "passive"))
    )
    (net (code "44") (name "SPI_CLK_MAIN_DUAL") (class "Default")
      (node (ref "IC31") (pin "2") (pinfunction "1Y_2") (pintype "passive"))
    )
    (net (code "45") (name "SPI_CLK_SMALL_A") (class "Default")
      (node (ref "IC29") (pin "6") (pinfunction "3Y_6") (pintype "passive"))
    )
    (net (code "46") (name "SPI_CLK_SMALL_B") (class "Default")
      (node (ref "IC29") (pin "8") (pinfunction "4Y_8") (pintype "passive"))
    )
    (net (code "47") (name "SPI_CLK_SMALL_DUAL") (class "Default")
      (node (ref "IC31") (pin "4") (pinfunction "2Y_4") (pintype "passive"))
    )
    (net (code "48") (name "SPI_CLKb_DUAL") (class "Default")
      (node (ref "IC25") (pin "3") (pinfunction "~{E}_3") (pintype "passive"))
    )
    (net (code "49") (name "SPI_CLKb_SINGLE") (class "Default")
      (node (ref "IC39") (pin "3") (pinfunction "~{E}_3") (pintype "passive"))
    )
    (net (code "50") (name "SPI_CSb_DUAL") (class "Default")
      (node (ref "IC26") (pin "3") (pinfunction "~{E}_3") (pintype "passive"))
    )
    (net (code "51") (name "SPI_CSb_MAIN_A") (class "Default")
      (node (ref "IC28") (pin "6") (pinfunction "Y0_6") (pintype "passive"))
    )
    (net (code "52") (name "SPI_CSb_MAIN_B") (class "Default")
      (node (ref "IC28") (pin "4") (pinfunction "Y1_4") (pintype "passive"))
    )
    (net (code "53") (name "SPI_CSb_MAIN_DUAL") (class "Default")
      (node (ref "IC26") (pin "6") (pinfunction "Y0_6") (pintype "passive"))
    )
    (net (code "54") (name "SPI_CSb_SINGLE") (class "Default")
      (node (ref "IC27") (pin "3") (pinfunction "~{E}_3") (pintype "passive"))
    )
    (net (code "55") (name "SPI_CSb_SMALL_A") (class "Default")
      (node (ref "IC30") (pin "6") (pinfunction "Y0_6") (pintype "passive"))
    )
    (net (code "56") (name "SPI_CSb_SMALL_B") (class "Default")
      (node (ref "IC30") (pin "4") (pinfunction "Y1_4") (pintype "passive"))
    )
    (net (code "57") (name "SPI_CSb_SMALL_DUAL") (class "Default")
      (node (ref "IC26") (pin "4") (pinfunction "Y1_4") (pintype "passive"))
    )
    (net (code "58") (name "SPI_DIN") (class "Default")
      (node (ref "R19") (pin "2") (pinfunction "2_2") (pintype "passive"))
      (node (ref "R20") (pin "2") (pinfunction "2_2") (pintype "passive"))
      (node (ref "R21") (pin "2") (pinfunction "2_2") (pintype "passive"))
      (node (ref "R22") (pin "2") (pinfunction "2_2") (pintype "passive"))
      (node (ref "R23") (pin "2") (pinfunction "2_2") (pintype "passive"))
      (node (ref "R24") (pin "2") (pinfunction "2_2") (pintype "passive"))
    )
    (net (code "59") (name "SPI_DIN_MAIN_DUAL") (class "Default")
      (node (ref "R19") (pin "1") (pinfunction "1_1") (pintype "passive"))
    )
    (net (code "60") (name "SPI_DIN_MAIN_SINGLE_A") (class "Default")
      (node (ref "R21") (pin "1") (pinfunction "1_1") (pintype "passive"))
    )
    (net (code "61") (name "SPI_DIN_MAIN_SINGLE_B") (class "Default")
      (node (ref "R22") (pin "1") (pinfunction "1_1") (pintype "passive"))
    )
    (net (code "62") (name "SPI_DIN_SMALL_DUAL") (class "Default")
      (node (ref "R20") (pin "1") (pinfunction "1_1") (pintype "passive"))
    )
    (net (code "63") (name "SPI_DIN_SMALL_SINGLE_A") (class "Default")
      (node (ref "R23") (pin "1") (pinfunction "1_1") (pintype "passive"))
    )
    (net (code "64") (name "SPI_DIN_SMALL_SINGLE_B") (class "Default")
      (node (ref "R24") (pin "1") (pinfunction "1_1") (pintype "passive"))
    )
    (net (code "65") (name "SPI_DOUT_DUAL") (class "Default")
      (node (ref "IC24") (pin "7") (pinfunction "1Y_7") (pintype "passive"))
    )
    (net (code "66") (name "SPI_DOUT_MAIN_A") (class "Default")
      (node (ref "IC22") (pin "10") (pinfunction "2C0_10") (pintype "passive"))
    )
    (net (code "67") (name "SPI_DOUT_MAIN_B") (class "Default")
      (node (ref "IC22") (pin "12") (pinfunction "2C2_12") (pintype "passive"))
    )
    (net (code "68") (name "SPI_DOUT_MAIN_DUAL") (class "Default")
      (node (ref "IC24") (pin "4") (pinfunction "1C2_4") (pintype "passive"))
      (node (ref "IC24") (pin "6") (pinfunction "1C0_6") (pintype "passive"))
    )
    (net (code "69") (name "SPI_DOUT_SINGLE") (class "Default")
      (node (ref "IC22") (pin "9") (pinfunction "2Y_9") (pintype "passive"))
    )
    (net (code "70") (name "SPI_DOUT_SMALL_A") (class "Default")
      (node (ref "IC22") (pin "11") (pinfunction "2C1_11") (pintype "passive"))
    )
    (net (code "71") (name "SPI_DOUT_SMALL_B") (class "Default")
      (node (ref "IC22") (pin "13") (pinfunction "2C3_13") (pintype "passive"))
    )
    (net (code "72") (name "SPI_DOUT_SMALL_DUAL") (class "Default")
      (node (ref "IC24") (pin "3") (pinfunction "1C3_3") (pintype "passive"))
      (node (ref "IC24") (pin "5") (pinfunction "1C1_5") (pintype "passive"))
    )
    (net (code "73") (name "TDC_EN_MAIN_A") (class "Default")
      (node (ref "IC31") (pin "6") (pinfunction "3Y_6") (pintype "passive"))
    )
    (net (code "74") (name "TDC_EN_MAIN_B") (class "Default")
      (node (ref "IC31") (pin "8") (pinfunction "4Y_8") (pintype "passive"))
    )
    (net (code "75") (name "TDC_EN_MAIN_DUAL") (class "Default")
      (node (ref "IC29") (pin "10") (pinfunction "5Y_10") (pintype "passive"))
    )
    (net (code "76") (name "TDC_EN_SMALL_A") (class "Default")
      (node (ref "IC31") (pin "10") (pinfunction "5Y_10") (pintype "passive"))
    )
    (net (code "77") (name "TDC_EN_SMALL_B") (class "Default")
      (node (ref "IC31") (pin "12") (pinfunction "6Y_12") (pintype "passive"))
    )
    (net (code "78") (name "TDC_EN_SMALL_DUAL") (class "Default")
      (node (ref "IC29") (pin "12") (pinfunction "6Y_12") (pintype "passive"))
    )
    (net (code "79") (name "TDC_ENb_DUAL") (class "Default")
      (node (ref "IC43") (pin "3") (pinfunction "~{E}_3") (pintype "passive"))
    )
    (net (code "80") (name "TDC_ENb_SINGLE") (class "Default")
      (node (ref "IC32") (pin "3") (pinfunction "~{E}_3") (pintype "passive"))
    )
    (net (code "81") (name "TDC_INTRb_DUAL") (class "Default")
      (node (ref "IC24") (pin "9") (pinfunction "2Y_9") (pintype "passive"))
    )
    (net (code "82") (name "TDC_INTRb_MAIN_A") (class "Default")
      (node (ref "IC23") (pin "6") (pinfunction "1C0_6") (pintype "passive"))
    )
    (net (code "83") (name "TDC_INTRb_MAIN_B") (class "Default")
      (node (ref "IC23") (pin "4") (pinfunction "1C2_4") (pintype "passive"))
    )
    (net (code "84") (name "TDC_INTRb_MAIN_DUAL") (class "Default")
      (node (ref "IC24") (pin "10") (pinfunction "2C0_10") (pintype "passive"))
      (node (ref "IC24") (pin "12") (pinfunction "2C2_12") (pintype "passive"))
    )
    (net (code "85") (name "TDC_INTRb_SINGLE") (class "Default")
      (node (ref "IC23") (pin "7") (pinfunction "1Y_7") (pintype "passive"))
    )
    (net (code "86") (name "TDC_INTRb_SMALL_A") (class "Default")
      (node (ref "IC23") (pin "5") (pinfunction "1C1_5") (pintype "passive"))
    )
    (net (code "87") (name "TDC_INTRb_SMALL_B") (class "Default")
      (node (ref "IC23") (pin "3") (pinfunction "1C3_3") (pintype "passive"))
    )
    (net (code "88") (name "TDC_INTRb_SMALL_DUAL") (class "Default")
      (node (ref "IC24") (pin "11") (pinfunction "2C1_11") (pintype "passive"))
      (node (ref "IC24") (pin "13") (pinfunction "2C3_13") (pintype "passive"))
    )
    (net (code "89") (name "TDC_TRIGG_DUAL") (class "Default")
      (node (ref "IC23") (pin "9") (pinfunction "2Y_9") (pintype "passive"))
    )
    (net (code "90") (name "TDC_TRIGG_MAIN_A") (class "Default")
      (node (ref "IC22") (pin "6") (pinfunction "1C0_6") (pintype "passive"))
    )
    (net (code "91") (name "TDC_TRIGG_MAIN_B") (class "Default")
      (node (ref "IC22") (pin "4") (pinfunction "1C2_4") (pintype "passive"))
    )
    (net (code "92") (name "TDC_TRIGG_MAIN_DUAL") (class "Default")
      (node (ref "IC23") (pin "10") (pinfunction "2C0_10") (pintype "passive"))
      (node (ref "IC23") (pin "12") (pinfunction "2C2_12") (pintype "passive"))
    )
    (net (code "93") (name "TDC_TRIGG_SINGLE") (class "Default")
      (node (ref "IC22") (pin "7") (pinfunction "1Y_7") (pintype "passive"))
    )
    (net (code "94") (name "TDC_TRIGG_SMALL_A") (class "Default")
      (node (ref "IC22") (pin "5") (pinfunction "1C1_5") (pintype "passive"))
    )
    (net (code "95") (name "TDC_TRIGG_SMALL_B") (class "Default")
      (node (ref "IC22") (pin "3") (pinfunction "1C3_3") (pintype "passive"))
    )
    (net (code "96") (name "TDC_TRIGG_SMALL_DUAL") (class "Default")
      (node (ref "IC23") (pin "11") (pinfunction "2C1_11") (pintype "passive"))
      (node (ref "IC23") (pin "13") (pinfunction "2C3_13") (pintype "passive"))
    )
    (net (code "97") (name "VREF_ATTEN_MAIN_A") (class "Default")
      (node (ref "P48") (pin "1") (pinfunction "1_1") (pintype "passive"))
    )
    (net (code "98") (name "VREF_ATTEN_MAIN_B") (class "Default")
      (node (ref "P48") (pin "2") (pinfunction "2_2") (pintype "passive"))
    )
    (net (code "99") (name "VRST_PK_TEST_A") (class "Default")
      (node (ref "P47") (pin "1") (pinfunction "1_1") (pintype "passive"))
    )
    (net (code "100") (name "VRST_PK_TEST_B") (class "Default")
      (node (ref "P47") (pin "2") (pinfunction "2_2") (pintype "passive"))
    )
    (net (code "101") (name "unconnected-(IC35-3Y-Pad6)") (class "Default")
      (node (ref "IC35") (pin "6") (pinfunction "3Y_6") (pintype "passive"))
    )
    (net (code "102") (name "unconnected-(IC35-4Y-Pad8)") (class "Default")
      (node (ref "IC35") (pin "8") (pinfunction "4Y_8") (pintype "passive"))
    )
    (net (code "103") (name "unconnected-(IC35-5Y-Pad10)") (class "Default")
      (node (ref "IC35") (pin "10") (pinfunction "5Y_10") (pintype "passive"))
    )
    (net (code "104") (name "unconnected-(IC35-6Y-Pad12)") (class "Default")
      (node (ref "IC35") (pin "12") (pinfunction "6Y_12") (pintype "passive"))
    )
    (net (code "105") (name "unconnected-(IC41-2Y-Pad9)") (class "Default")
      (node (ref "IC41") (pin "9") (pinfunction "2Y_9") (pintype "passive"))
    )
  )
)
